# UD3_1.net
KiCad netlist of a schematic drawn in Altium Designer
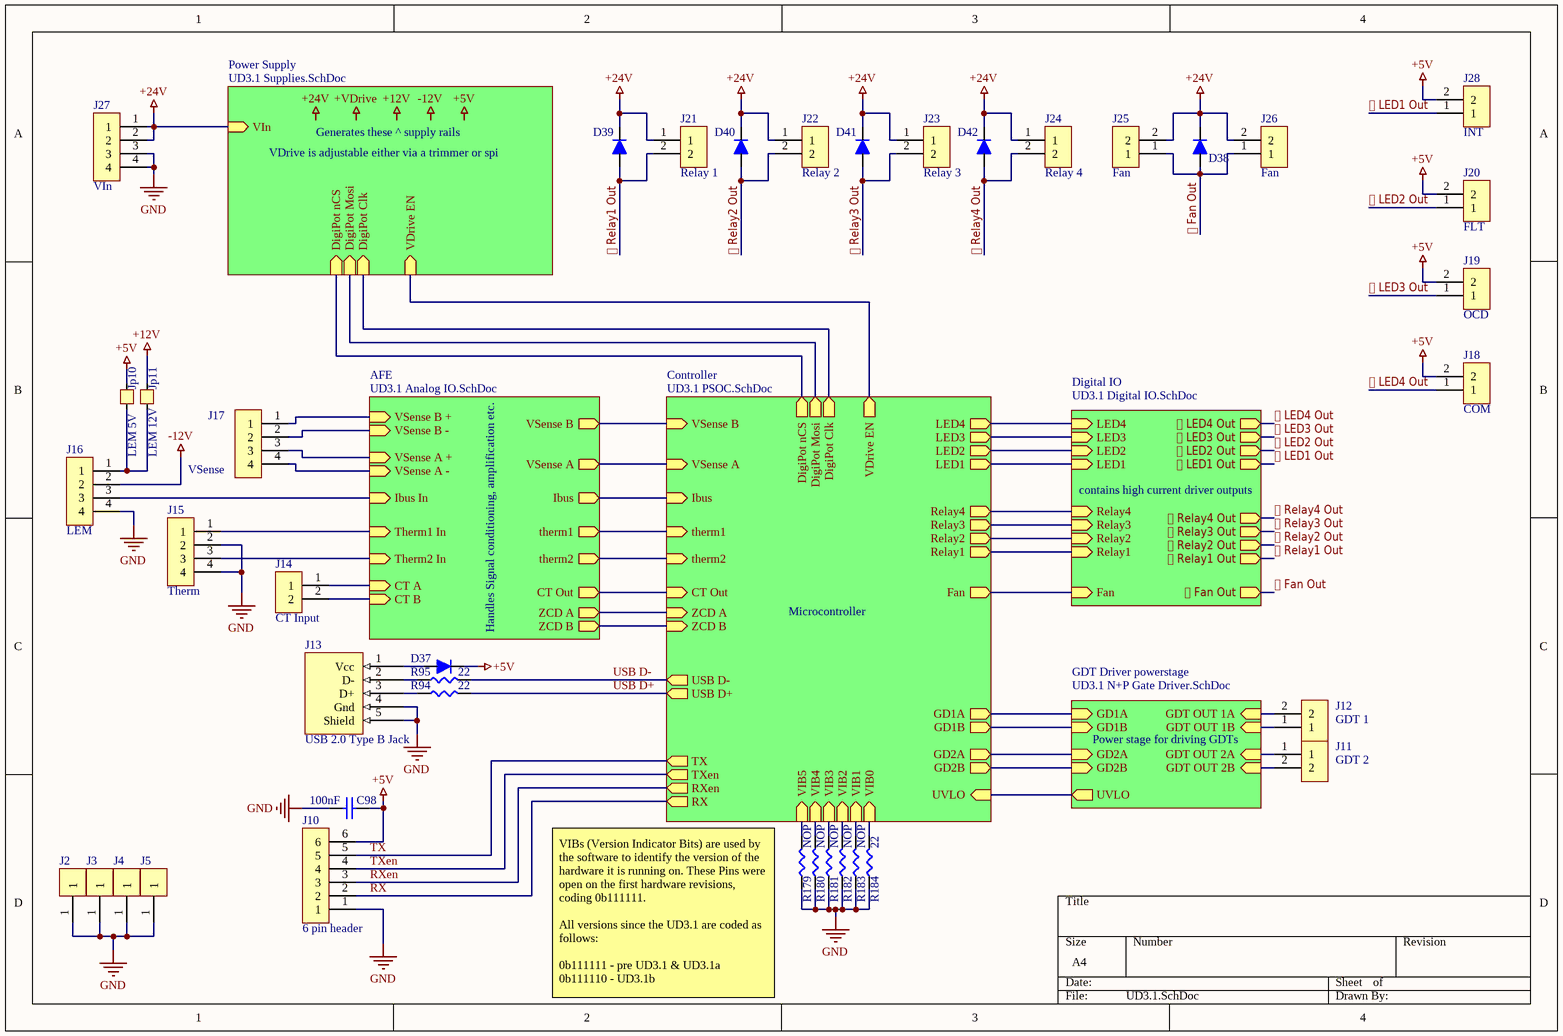
[diagram p0: UD3.1.SchDoc]

(export (version "E")
  (design (tool "Eeschema 10.0.6"))
  (components
    (comp (ref "C98") (value "100nF") (footprint "0603") (libsource (lib "stdLib") (part "Cap")))
    (comp (ref "D37")
      (value "Schottky 30V 1A")
      (footprint "DO-214")
      (description "Cmon its a diode what more do I need to say?")
      (libsource (lib "stdLib") (part "Diode"))
    )
    (comp (ref "D38")
      (value "Schottky 30V 1A")
      (footprint "DO-214")
      (description "Cmon its a diode what more do I need to say?")
      (libsource (lib "stdLib") (part "Diode"))
    )
    (comp (ref "D39")
      (value "Schottky 30V 100mA")
      (footprint "SOD523")
      (description "Cmon its a diode what more do I need to say?")
      (libsource (lib "stdLib") (part "Diode"))
    )
    (comp (ref "D40")
      (value "Schottky 30V 100mA")
      (footprint "SOD523")
      (description "Cmon its a diode what more do I need to say?")
      (libsource (lib "stdLib") (part "Diode"))
    )
    (comp (ref "D41")
      (value "Schottky 30V 100mA")
      (footprint "SOD523")
      (description "Cmon its a diode what more do I need to say?")
      (libsource (lib "stdLib") (part "Diode"))
    )
    (comp (ref "D42")
      (value "Schottky 30V 100mA")
      (footprint "SOD523")
      (description "Cmon its a diode what more do I need to say?")
      (libsource (lib "stdLib") (part "Diode"))
    )
    (comp (ref "J2") (value "GND Pad") (footprint "1 Pad M3") (libsource (lib "stdCon") (part "1 Header")))
    (comp (ref "J3") (value "GND Pad") (footprint "1 Pad M3") (libsource (lib "stdCon") (part "1 Header")))
    (comp (ref "J4") (value "GND Pad") (footprint "1 Pad M3") (libsource (lib "stdCon") (part "1 Header")))
    (comp (ref "J5") (value "GND Pad") (footprint "1 Pad M3") (libsource (lib "stdCon") (part "1 Header")))
    (comp (ref "J10")
      (value "6 pin header")
      (footprint "6 KK254 / KF2510")
      (libsource (lib "stdCon") (part "6 header"))
    )
    (comp (ref "J11") (value "GDT 2") (footprint "2 KK254 / KF2510") (libsource (lib "") (part "2 header_2")))
    (comp (ref "J12") (value "GDT 1") (footprint "2 KK254 / KF2510") (libsource (lib "") (part "2 header_1")))
    (comp (ref "J13")
      (value "USB 2.0 Type B Jack")
      (footprint "USB 2.0 Type B Vertical")
      (libsource (lib "stdCon") (part "USB 2.0 Type B"))
    )
    (comp (ref "J14")
      (value "CT Input")
      (footprint "2 KK254 / KF2510")
      (libsource (lib "stdCon") (part "2 header"))
    )
    (comp (ref "J15")
      (value "Therm")
      (footprint "4 KK254 / KF2510")
      (libsource (lib "stdCon") (part "4 header"))
    )
    (comp (ref "J16")
      (value "LEM")
      (footprint "4 KK254 / KF2510")
      (libsource (lib "stdCon") (part "4 header"))
    )
    (comp (ref "J17")
      (value "VSense")
      (footprint "4 KK254 / KF2510")
      (libsource (lib "stdCon") (part "4 header"))
    )
    (comp (ref "J18") (value "COM") (footprint "2 KK254 / KF2510") (libsource (lib "") (part "2 header_1")))
    (comp (ref "J19") (value "OCD") (footprint "2 KK254 / KF2510") (libsource (lib "") (part "2 header_1")))
    (comp (ref "J20") (value "FLT") (footprint "2 KK254 / KF2510") (libsource (lib "") (part "2 header_1")))
    (comp (ref "J21")
      (value "Relay 1")
      (footprint "2 KK254 / KF2510")
      (libsource (lib "") (part "2 header_2"))
    )
    (comp (ref "J22")
      (value "Relay 2")
      (footprint "2 KK254 / KF2510")
      (libsource (lib "") (part "2 header_2"))
    )
    (comp (ref "J23")
      (value "Relay 3")
      (footprint "2 KK254 / KF2510")
      (libsource (lib "") (part "2 header_2"))
    )
    (comp (ref "J24")
      (value "Relay 4")
      (footprint "2 KK254 / KF2510")
      (libsource (lib "") (part "2 header_2"))
    )
    (comp (ref "J25") (value "Fan") (footprint "2 KK254 / KF2510") (libsource (lib "") (part "2 header_3")))
    (comp (ref "J26")
      (value "Fan")
      (footprint "2 screw terminal vertical")
      (libsource (lib "stdCon") (part "2 screw terminal"))
    )
    (comp (ref "J27")
      (value "VIn")
      (footprint "4 KK254 / KF2510")
      (libsource (lib "stdCon") (part "4 header"))
    )
    (comp (ref "J28") (value "INT") (footprint "2 KK254 / KF2510") (libsource (lib "") (part "2 header_1")))
    (comp (ref "Jp10")
      (value "LEM 5V")
      (footprint "PCB Jumper NO")
      (libsource (lib "stdLib") (part "Jumper"))
    )
    (comp (ref "Jp11")
      (value "LEM 12V")
      (footprint "PCB Jumper NO")
      (libsource (lib "stdLib") (part "Jumper"))
    )
    (comp (ref "R94") (value "22") (footprint "0603") (libsource (lib "stdLib") (part "Resistor")))
    (comp (ref "R95") (value "22") (footprint "0603") (libsource (lib "stdLib") (part "Resistor")))
    (comp (ref "R179") (value "NOP") (footprint "0603") (libsource (lib "stdLib") (part "Resistor")))
    (comp (ref "R180") (value "NOP") (footprint "0603") (libsource (lib "stdLib") (part "Resistor")))
    (comp (ref "R181") (value "NOP") (footprint "0603") (libsource (lib "stdLib") (part "Resistor")))
    (comp (ref "R182") (value "NOP") (footprint "0603") (libsource (lib "stdLib") (part "Resistor")))
    (comp (ref "R183") (value "NOP") (footprint "0603") (libsource (lib "stdLib") (part "Resistor")))
    (comp (ref "R184") (value "22") (footprint "0603") (libsource (lib "stdLib") (part "Resistor")))
  )
  (nets
    (net (code "1") (name "+5V") (class "Default")
      (node (ref "C98") (pin "1") (pinfunction "1_1") (pintype "passive"))
      (node (ref "D37") (pin "2") (pintype "passive"))
      (node (ref "J10") (pin "6") (pinfunction "6_6") (pintype "passive"))
      (node (ref "J18") (pin "2") (pinfunction "2_2") (pintype "passive"))
      (node (ref "J19") (pin "2") (pinfunction "2_2") (pintype "passive"))
      (node (ref "J20") (pin "2") (pinfunction "2_2") (pintype "passive"))
      (node (ref "J28") (pin "2") (pinfunction "2_2") (pintype "passive"))
      (node (ref "Jp10") (pin "2") (pinfunction "2_2") (pintype "passive"))
    )
    (net (code "2") (name "+12V") (class "Default")
      (node (ref "Jp11") (pin "2") (pinfunction "2_2") (pintype "passive"))
    )
    (net (code "3") (name "+24V") (class "Default")
      (node (ref "D38") (pin "2") (pintype "passive"))
      (node (ref "D39") (pin "2") (pintype "passive"))
      (node (ref "D40") (pin "2") (pintype "passive"))
      (node (ref "D41") (pin "2") (pintype "passive"))
      (node (ref "D42") (pin "2") (pintype "passive"))
      (node (ref "J21") (pin "1") (pinfunction "1_1") (pintype "passive"))
      (node (ref "J22") (pin "1") (pinfunction "1_1") (pintype "passive"))
      (node (ref "J23") (pin "1") (pinfunction "1_1") (pintype "passive"))
      (node (ref "J24") (pin "1") (pinfunction "1_1") (pintype "passive"))
      (node (ref "J25") (pin "2") (pinfunction "2_2") (pintype "passive"))
      (node (ref "J26") (pin "2") (pinfunction "2_2") (pintype "passive"))
      (node (ref "J27") (pin "1") (pinfunction "1_1") (pintype "passive"))
      (node (ref "J27") (pin "2") (pinfunction "2_2") (pintype "passive"))
    )
    (net (code "5") (name "-12V") (class "Default")
      (node (ref "J16") (pin "2") (pinfunction "2_2") (pintype "passive"))
    )
    (net (code "6") (name "/CT A") (class "Default")
      (node (ref "J14") (pin "1") (pinfunction "1_1") (pintype "passive"))
    )
    (net (code "7") (name "/CT B") (class "Default")
      (node (ref "J14") (pin "2") (pinfunction "2_2") (pintype "passive"))
    )
    (net (code "17") (name "/GDT OUT 1A") (class "Default")
      (node (ref "J12") (pin "2") (pinfunction "2_2") (pintype "passive"))
    )
    (net (code "18") (name "/GDT OUT 1B") (class "Default")
      (node (ref "J12") (pin "1") (pinfunction "1_1") (pintype "passive"))
    )
    (net (code "19") (name "/GDT OUT 2A") (class "Default")
      (node (ref "J11") (pin "1") (pinfunction "1_1") (pintype "passive"))
    )
    (net (code "20") (name "/GDT OUT 2B") (class "Default")
      (node (ref "J11") (pin "2") (pinfunction "2_2") (pintype "passive"))
    )
    (net (code "22") (name "/Ibus In") (class "Default")
      (node (ref "J16") (pin "3") (pinfunction "3_3") (pintype "passive"))
    )
    (net (code "27") (name "/RX") (class "Default")
      (node (ref "J10") (pin "2") (pinfunction "2_2") (pintype "passive"))
    )
    (net (code "28") (name "/RXen") (class "Default")
      (node (ref "J10") (pin "3") (pinfunction "3_3") (pintype "passive"))
    )
    (net (code "33") (name "/TX") (class "Default")
      (node (ref "J10") (pin "5") (pinfunction "5_5") (pintype "passive"))
    )
    (net (code "34") (name "/TXen") (class "Default")
      (node (ref "J10") (pin "4") (pinfunction "4_4") (pintype "passive"))
    )
    (net (code "35") (name "/Therm1 In") (class "Default")
      (node (ref "J15") (pin "1") (pinfunction "1_1") (pintype "passive"))
    )
    (net (code "36") (name "/Therm2 In") (class "Default")
      (node (ref "J15") (pin "3") (pinfunction "3_3") (pintype "passive"))
    )
    (net (code "37") (name "/USB D+") (class "Default")
      (node (ref "R94") (pin "1") (pinfunction "1_1") (pintype "passive"))
    )
    (net (code "38") (name "/USB D-") (class "Default")
      (node (ref "R95") (pin "1") (pinfunction "1_1") (pintype "passive"))
    )
    (net (code "41") (name "/VIB0") (class "Default")
      (node (ref "R184") (pin "1") (pinfunction "1_1") (pintype "passive"))
    )
    (net (code "42") (name "/VIB1") (class "Default")
      (node (ref "R183") (pin "1") (pinfunction "1_1") (pintype "passive"))
    )
    (net (code "43") (name "/VIB2") (class "Default")
      (node (ref "R182") (pin "1") (pinfunction "1_1") (pintype "passive"))
    )
    (net (code "44") (name "/VIB3") (class "Default")
      (node (ref "R181") (pin "1") (pinfunction "1_1") (pintype "passive"))
    )
    (net (code "45") (name "/VIB4") (class "Default")
      (node (ref "R180") (pin "1") (pinfunction "1_1") (pintype "passive"))
    )
    (net (code "46") (name "/VIB5") (class "Default")
      (node (ref "R179") (pin "1") (pinfunction "1_1") (pintype "passive"))
    )
    (net (code "48") (name "/VSense A +") (class "Default")
      (node (ref "J17") (pin "3") (pinfunction "3_3") (pintype "passive"))
    )
    (net (code "49") (name "/VSense A -") (class "Default")
      (node (ref "J17") (pin "4") (pinfunction "4_4") (pintype "passive"))
    )
    (net (code "51") (name "/VSense B +") (class "Default")
      (node (ref "J17") (pin "1") (pinfunction "1_1") (pintype "passive"))
    )
    (net (code "52") (name "/VSense B -") (class "Default")
      (node (ref "J17") (pin "2") (pinfunction "2_2") (pintype "passive"))
    )
    (net (code "57") (name "/⎐ Fan Out") (class "Default")
      (node (ref "D38") (pin "1") (pintype "passive"))
      (node (ref "J25") (pin "1") (pinfunction "1_1") (pintype "passive"))
      (node (ref "J26") (pin "1") (pinfunction "1_1") (pintype "passive"))
    )
    (net (code "58") (name "/⎐ LED1 Out") (class "Default")
      (node (ref "J28") (pin "1") (pinfunction "1_1") (pintype "passive"))
    )
    (net (code "59") (name "/⎐ LED2 Out") (class "Default")
      (node (ref "J20") (pin "1") (pinfunction "1_1") (pintype "passive"))
    )
    (net (code "60") (name "/⎐ LED3 Out") (class "Default")
      (node (ref "J19") (pin "1") (pinfunction "1_1") (pintype "passive"))
    )
    (net (code "61") (name "/⎐ LED4 Out") (class "Default")
      (node (ref "J18") (pin "1") (pinfunction "1_1") (pintype "passive"))
    )
    (net (code "62") (name "/⎐ Relay1 Out") (class "Default")
      (node (ref "D39") (pin "1") (pintype "passive"))
      (node (ref "J21") (pin "2") (pinfunction "2_2") (pintype "passive"))
    )
    (net (code "63") (name "/⎐ Relay2 Out") (class "Default")
      (node (ref "D40") (pin "1") (pintype "passive"))
      (node (ref "J22") (pin "2") (pinfunction "2_2") (pintype "passive"))
    )
    (net (code "64") (name "/⎐ Relay3 Out") (class "Default")
      (node (ref "D41") (pin "1") (pintype "passive"))
      (node (ref "J23") (pin "2") (pinfunction "2_2") (pintype "passive"))
    )
    (net (code "65") (name "/⎐ Relay4 Out") (class "Default")
      (node (ref "D42") (pin "1") (pintype "passive"))
      (node (ref "J24") (pin "2") (pinfunction "2_2") (pintype "passive"))
    )
    (net (code "66") (name "GND") (class "Default")
      (node (ref "C98") (pin "2") (pinfunction "2_2") (pintype "passive"))
      (node (ref "J10") (pin "1") (pinfunction "1_1") (pintype "passive"))
      (node (ref "J13") (pin "4") (pinfunction "Gnd_4") (pintype "input"))
      (node (ref "J13") (pin "5") (pinfunction "Shield_5") (pintype "input"))
      (node (ref "J15") (pin "2") (pinfunction "2_2") (pintype "passive"))
      (node (ref "J15") (pin "4") (pinfunction "4_4") (pintype "passive"))
      (node (ref "J16") (pin "4") (pinfunction "4_4") (pintype "passive"))
      (node (ref "J2") (pin "1") (pinfunction "1_1") (pintype "passive"))
      (node (ref "J27") (pin "3") (pinfunction "3_3") (pintype "passive"))
      (node (ref "J27") (pin "4") (pinfunction "4_4") (pintype "passive"))
      (node (ref "J3") (pin "1") (pinfunction "1_1") (pintype "passive"))
      (node (ref "J4") (pin "1") (pinfunction "1_1") (pintype "passive"))
      (node (ref "J5") (pin "1") (pinfunction "1_1") (pintype "passive"))
      (node (ref "R179") (pin "2") (pinfunction "2_2") (pintype "passive"))
      (node (ref "R180") (pin "2") (pinfunction "2_2") (pintype "passive"))
      (node (ref "R181") (pin "2") (pinfunction "2_2") (pintype "passive"))
      (node (ref "R182") (pin "2") (pinfunction "2_2") (pintype "passive"))
      (node (ref "R183") (pin "2") (pinfunction "2_2") (pintype "passive"))
      (node (ref "R184") (pin "2") (pinfunction "2_2") (pintype "passive"))
    )
    (net (code "67") (name "Net-(J13-D+)") (class "Default")
      (node (ref "J13") (pin "3") (pinfunction "D+_3") (pintype "input"))
      (node (ref "R94") (pin "2") (pinfunction "2_2") (pintype "passive"))
    )
    (net (code "68") (name "Net-(J13-D-)") (class "Default")
      (node (ref "J13") (pin "2") (pinfunction "D-_2") (pintype "input"))
      (node (ref "R95") (pin "2") (pinfunction "2_2") (pintype "passive"))
    )
    (net (code "69") (name "Net-(J13-Vcc)") (class "Default")
      (node (ref "D37") (pin "1") (pintype "passive"))
      (node (ref "J13") (pin "1") (pinfunction "Vcc_1") (pintype "input"))
    )
    (net (code "70") (name "Net-(J16-Pad1)") (class "Default")
      (node (ref "J16") (pin "1") (pinfunction "1_1") (pintype "passive"))
      (node (ref "Jp10") (pin "1") (pinfunction "1_1") (pintype "passive"))
      (node (ref "Jp11") (pin "1") (pinfunction "1_1") (pintype "passive"))
    )
  )
)
